# SurfaceEEG_E_V1_3.net
KiCad netlist of a schematic drawn in EAGLE
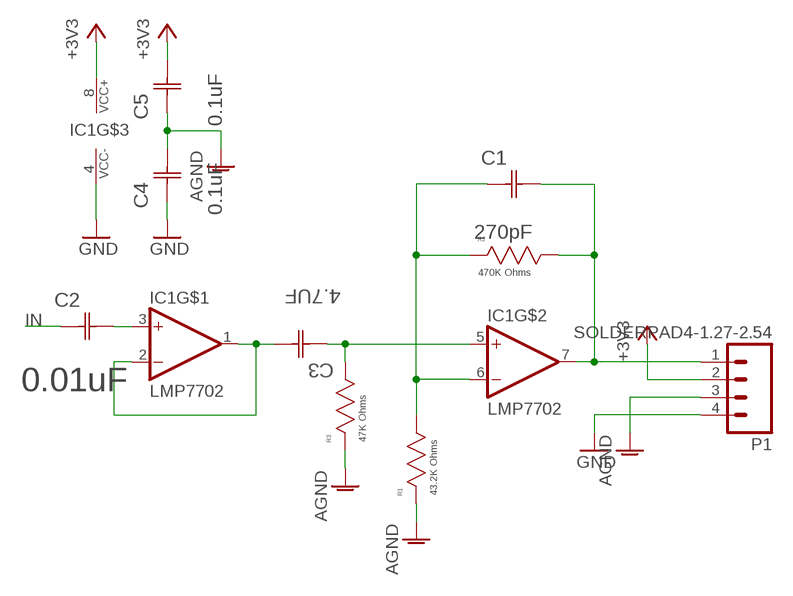
[diagram p0: schematic, sheet 1]

(export (version "E")
  (design (tool "Eeschema 10.0.6"))
  (components
    (comp (ref "C1")
      (value "270pF")
      (footprint "eagle-import:CAPC1608X90N")
      (fields (field (name "MPN") "06035A271JAT2A") (field (name "TOLERANCE") "± 5%"))
      (libsource (lib "eagle-import") (part "06035A271JAT2A"))
    )
    (comp (ref "C2")
      (value "0.01uF")
      (footprint "eagle-import:CAPC1005X60N")
      (fields (field (name "MPN") "C0402C103J3RACTU") (field (name "TOLERANCE") "±5%"))
      (libsource (lib "eagle-import") (part "C0402C103J3RACTU"))
    )
    (comp (ref "C3")
      (value "4.7UF")
      (footprint "eagle-import:CAPC1608X90N")
      (fields (field (name "MPN") "06036D475MAT2A") (field (name "TOLERANCE") "±20%"))
      (libsource (lib "eagle-import") (part "06036D475MAT2A"))
    )
    (comp (ref "C4")
      (value "0.1uF")
      (footprint "eagle-import:CAPC1005X60N")
      (fields (field (name "MPN") "04023C104KAT2A") (field (name "TOLERANCE") "±10%"))
      (libsource (lib "eagle-import") (part "04023C104KAT2A"))
    )
    (comp (ref "C5")
      (value "0.1uF")
      (footprint "eagle-import:CAPC1005X60N")
      (fields (field (name "MPN") "04023C104KAT2A") (field (name "TOLERANCE") "±10%"))
      (libsource (lib "eagle-import") (part "04023C104KAT2A"))
    )
    (comp (ref "IC1")
      (value "LMP7702")
      (footprint "eagle-import:VSSOP8")
      (fields (field (name "MPN") "LMP7702MM/NOPB"))
      (libsource (lib "eagle-import") (part "LMP7702"))
    )
    (comp (ref "P1")
      (value "SOLDERPAD4-1.27-2.54")
      (footprint "eagle-import:SMD1,27-2,54")
      (libsource (lib "eagle-import") (part "SOLDERPAD4-1.27-2.54"))
    )
    (comp (ref "R1")
      (value "43.2K Ohms")
      (footprint "eagle-import:RESC1608X60N")
      (fields (field (name "MPN") "RC0603FR-0743K2L") (field (name "TOLERANCE") "±1%"))
      (libsource (lib "eagle-import") (part "RC0603FR-0743K2L"))
    )
    (comp (ref "R2")
      (value "470K Ohms")
      (footprint "eagle-import:RESC1608X60N")
      (fields (field (name "MPN") "RC0603FR-07470KL") (field (name "TOLERANCE") "±1%"))
      (libsource (lib "eagle-import") (part "RC0603FR-07470KL"))
    )
    (comp (ref "R3")
      (value "47K Ohms")
      (footprint "eagle-import:RESC1608X60N")
      (fields (field (name "MPN") "RC0603FR-0747KL") (field (name "TOLERANCE") "±1%"))
      (libsource (lib "eagle-import") (part "RC0603FR-0747KL"))
    )
  )
  (nets
    (net (code "1") (name "+3V3") (class "Default")
      (node (ref "C5") (pin "1") (pinfunction "C2_1") (pintype "passive"))
      (node (ref "IC1") (pin "8") (pinfunction "VCC+_8") (pintype "power_in"))
      (node (ref "P1") (pin "2") (pinfunction "2_2") (pintype "passive"))
    )
    (net (code "2") (name "/IN") (class "Default")
      (node (ref "C2") (pin "1") (pinfunction "C1_1") (pintype "passive"))
    )
    (net (code "3") (name "AGND") (class "Default")
      (node (ref "C4") (pin "1") (pinfunction "C2_1") (pintype "passive"))
      (node (ref "C5") (pin "2") (pinfunction "C1_2") (pintype "passive"))
      (node (ref "P1") (pin "3") (pinfunction "3_3") (pintype "passive"))
      (node (ref "R1") (pin "2") (pinfunction "R2_2") (pintype "passive"))
      (node (ref "R3") (pin "2") (pinfunction "R2_2") (pintype "passive"))
    )
    (net (code "4") (name "GND") (class "Default")
      (node (ref "C4") (pin "2") (pinfunction "C1_2") (pintype "passive"))
      (node (ref "IC1") (pin "4") (pinfunction "VCC-_4") (pintype "power_in"))
      (node (ref "P1") (pin "4") (pinfunction "4_4") (pintype "passive"))
    )
    (net (code "5") (name "Net-(C1-C1)") (class "Default")
      (node (ref "C1") (pin "1") (pinfunction "C1_1") (pintype "passive"))
      (node (ref "IC1") (pin "6") (pinfunction "IN-_6") (pintype "input"))
      (node (ref "R1") (pin "1") (pinfunction "R1_1") (pintype "passive"))
      (node (ref "R2") (pin "2") (pinfunction "R2_2") (pintype "passive"))
    )
    (net (code "6") (name "Net-(C1-C2)") (class "Default")
      (node (ref "C1") (pin "2") (pinfunction "C2_2") (pintype "passive"))
      (node (ref "IC1") (pin "7") (pinfunction "OUT_7") (pintype "output"))
      (node (ref "P1") (pin "1") (pinfunction "1_1") (pintype "passive"))
      (node (ref "R2") (pin "1") (pinfunction "R1_1") (pintype "passive"))
    )
    (net (code "7") (name "Net-(C2-C2)") (class "Default")
      (node (ref "C2") (pin "2") (pinfunction "C2_2") (pintype "passive"))
      (node (ref "IC1") (pin "3") (pinfunction "IN+_3") (pintype "input"))
    )
    (net (code "8") (name "Net-(C3-C1)") (class "Default")
      (node (ref "C3") (pin "1") (pinfunction "C1_1") (pintype "passive"))
      (node (ref "IC1") (pin "5") (pinfunction "IN+_5") (pintype "input"))
      (node (ref "R3") (pin "1") (pinfunction "R1_1") (pintype "passive"))
    )
    (net (code "9") (name "Net-(C3-C2)") (class "Default")
      (node (ref "C3") (pin "2") (pinfunction "C2_2") (pintype "passive"))
      (node (ref "IC1") (pin "1") (pinfunction "OUT_1") (pintype "output"))
      (node (ref "IC1") (pin "2") (pinfunction "IN-_2") (pintype "input"))
    )
  )
)
